# PiZeroHifi.net
KiCad netlist of a schematic drawn in EAGLE
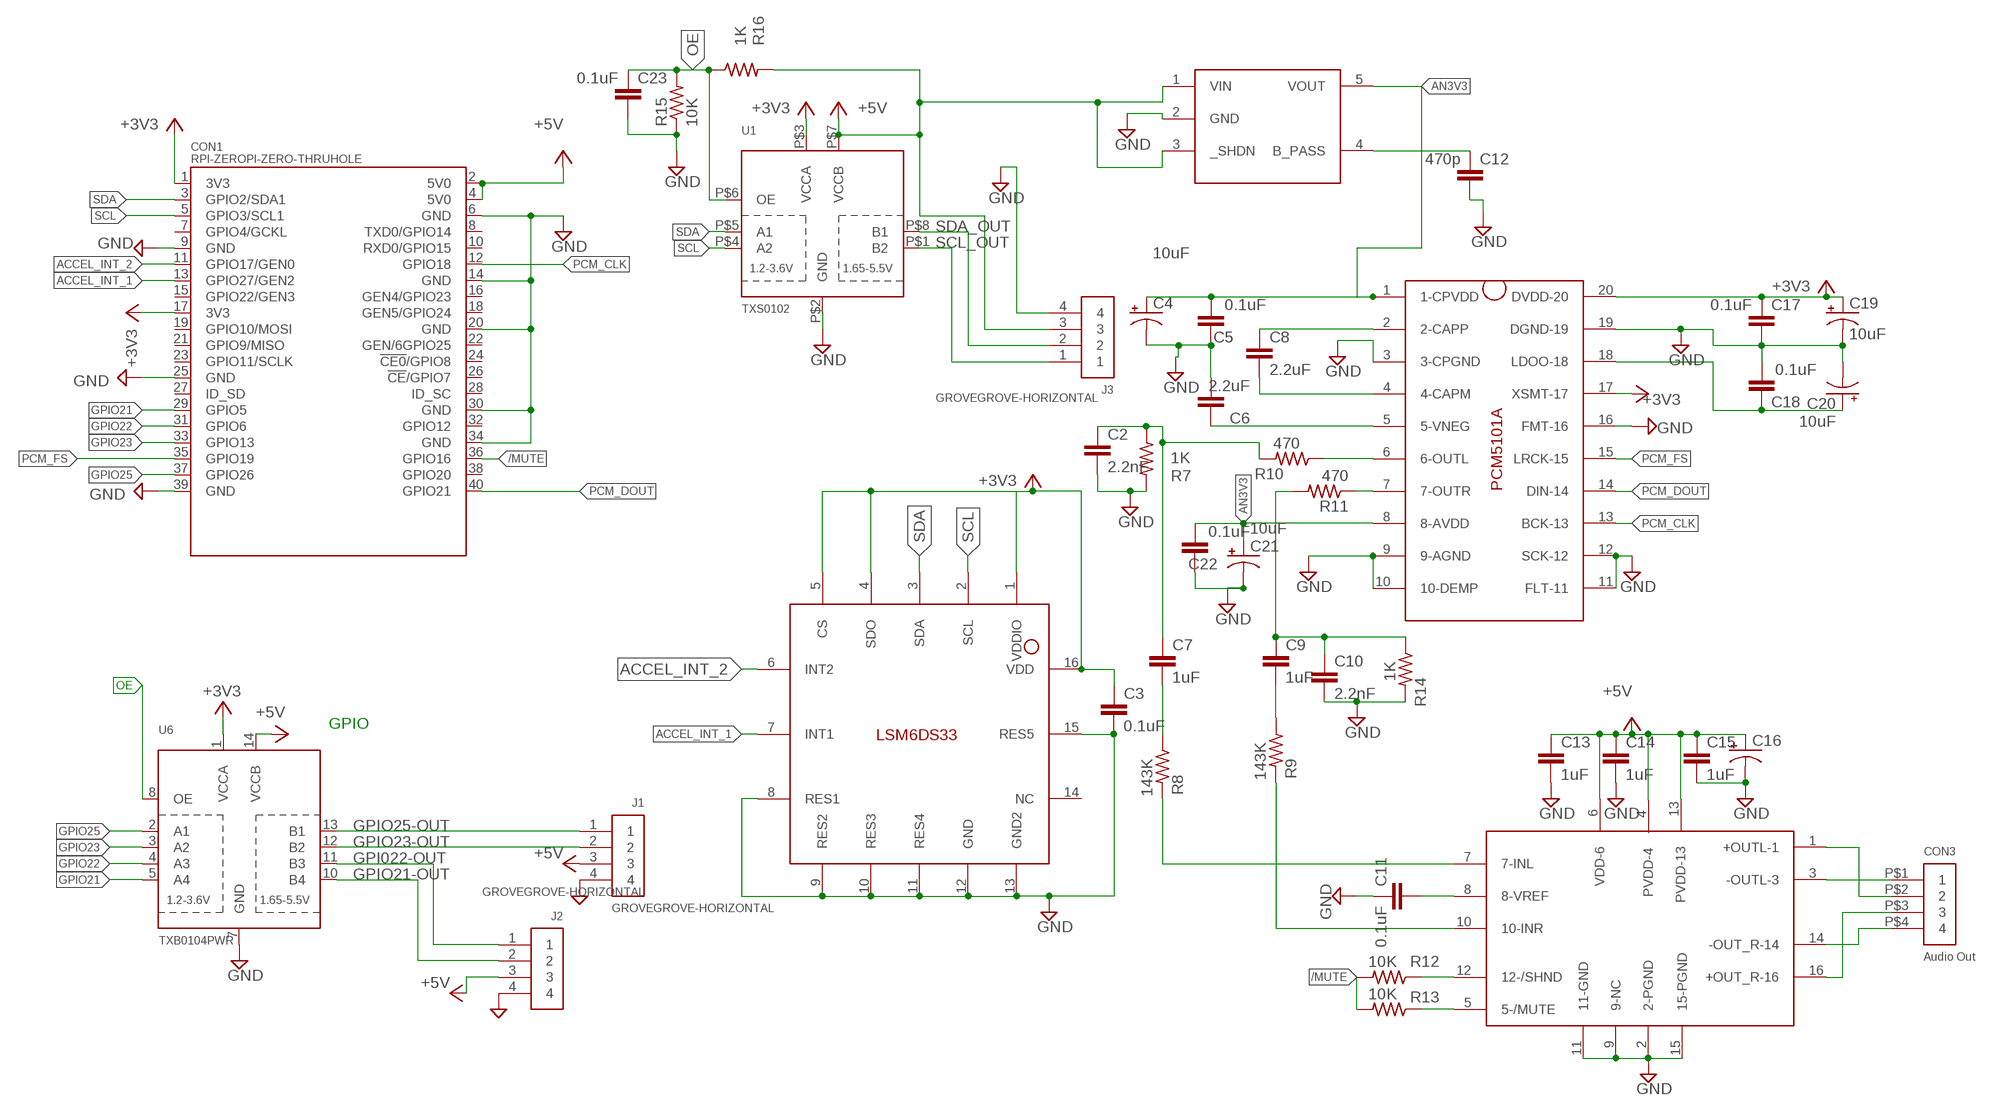
[diagram p0: schematic, sheet 1]

(export (version "E")
  (design (tool "Eeschema 10.0.6"))
  (components
    (comp (ref "C2")
      (value "2.2nF")
      (footprint "eagle-import:C0603")
      (fields (field (name "MF") "YAGEO") (field (name "MPN") "CC0603KRX7R9BB222"))
      (libsource (lib "eagle-import") (part "C-EUC0603"))
    )
    (comp (ref "C3")
      (value "0.1uF")
      (footprint "eagle-import:C0603")
      (fields (field (name "MF") "YAGEO") (field (name "MPN") "CC0603KRX7R7BB104"))
      (libsource (lib "eagle-import") (part "C-EUC0603"))
    )
    (comp (ref "C4")
      (value "10uF")
      (footprint "eagle-import:EIA3216")
      (fields (field (name "MF") "AVX") (field (name "MPN") "08053D106KAT2A"))
      (libsource (lib "eagle-import") (part "CAP-POLARISED1206-POLAR"))
    )
    (comp (ref "C5")
      (value "0.1uF")
      (footprint "eagle-import:C0603")
      (fields (field (name "MF") "YAGEO") (field (name "MPN") "CC0603KRX7R7BB104"))
      (libsource (lib "eagle-import") (part "C-EUC0603"))
    )
    (comp (ref "C6")
      (value "2.2uF")
      (footprint "eagle-import:C0603")
      (libsource (lib "eagle-import") (part "C-EUC0603"))
    )
    (comp (ref "C7")
      (value "1uF")
      (footprint "eagle-import:C0603")
      (fields (field (name "MF") "AVX") (field (name "MPN") "06033C104JAT2A"))
      (libsource (lib "eagle-import") (part "C-EUC0603"))
    )
    (comp (ref "C8")
      (value "2.2uF")
      (footprint "eagle-import:C0603")
      (libsource (lib "eagle-import") (part "C-EUC0603"))
    )
    (comp (ref "C9")
      (value "1uF")
      (footprint "eagle-import:C0603")
      (fields (field (name "MF") "AVX") (field (name "MPN") "06033C104JAT2A"))
      (libsource (lib "eagle-import") (part "C-EUC0603"))
    )
    (comp (ref "C10")
      (value "2.2nF")
      (footprint "eagle-import:C0603")
      (fields (field (name "MF") "YAGEO") (field (name "MPN") "CC0603KRX7R9BB222"))
      (libsource (lib "eagle-import") (part "C-EUC0603"))
    )
    (comp (ref "C11")
      (value "0.1uF")
      (footprint "eagle-import:C0603")
      (fields (field (name "MF") "YAGEO") (field (name "MPN") "CC0603KRX7R7BB104"))
      (libsource (lib "eagle-import") (part "C-EUC0603"))
    )
    (comp (ref "C12")
      (value "470p")
      (footprint "eagle-import:C0603")
      (fields (field (name "MF") "AVX") (field (name "MPN") "06035C471KAT2A"))
      (libsource (lib "eagle-import") (part "C-EUC0603"))
    )
    (comp (ref "C13")
      (value "1uF")
      (footprint "eagle-import:C0603")
      (fields (field (name "MF") "AVX") (field (name "MPN") "06033C104JAT2A"))
      (libsource (lib "eagle-import") (part "C-EUC0603"))
    )
    (comp (ref "C14")
      (value "1uF")
      (footprint "eagle-import:C0603")
      (fields (field (name "MF") "AVX") (field (name "MPN") "06033C104JAT2A"))
      (libsource (lib "eagle-import") (part "C-EUC0603"))
    )
    (comp (ref "C15")
      (value "1uF")
      (footprint "eagle-import:C0603")
      (fields (field (name "MF") "AVX") (field (name "MPN") "06033C104JAT2A"))
      (libsource (lib "eagle-import") (part "C-EUC0603"))
    )
    (comp (ref "C16")
      (value "1500uF")
      (footprint "eagle-import:CAP8MMX3.5MMX20MM")
      (libsource (lib "eagle-import") (part "WURTH-CAP"))
    )
    (comp (ref "C17")
      (value "0.1uF")
      (footprint "eagle-import:C0603")
      (fields (field (name "MF") "YAGEO") (field (name "MPN") "CC0603KRX7R7BB104"))
      (libsource (lib "eagle-import") (part "C-EUC0603"))
    )
    (comp (ref "C18")
      (value "0.1uF")
      (footprint "eagle-import:C0603")
      (fields (field (name "MF") "YAGEO") (field (name "MPN") "CC0603KRX7R7BB104"))
      (libsource (lib "eagle-import") (part "C-EUC0603"))
    )
    (comp (ref "C19")
      (value "10uF")
      (footprint "eagle-import:EIA3216")
      (fields (field (name "MF") "AVX") (field (name "MPN") "08053D106KAT2A"))
      (libsource (lib "eagle-import") (part "CAP-POLARISED1206-POLAR"))
    )
    (comp (ref "C20")
      (value "10uF")
      (footprint "eagle-import:EIA3216")
      (fields (field (name "MF") "AVX") (field (name "MPN") "08053D106KAT2A"))
      (libsource (lib "eagle-import") (part "CAP-POLARISED1206-POLAR"))
    )
    (comp (ref "C21")
      (value "10uF")
      (footprint "eagle-import:EIA3216")
      (fields (field (name "MF") "AVX") (field (name "MPN") "08053D106KAT2A"))
      (libsource (lib "eagle-import") (part "CAP-POLARISED1206-POLAR"))
    )
    (comp (ref "C22")
      (value "0.1uF")
      (footprint "eagle-import:C0603")
      (fields (field (name "MF") "YAGEO") (field (name "MPN") "CC0603KRX7R7BB104"))
      (libsource (lib "eagle-import") (part "C-EUC0603"))
    )
    (comp (ref "C23")
      (value "0.1uF")
      (footprint "eagle-import:C0603")
      (fields (field (name "MF") "YAGEO") (field (name "MPN") "CC0603KRX7R7BB104"))
      (libsource (lib "eagle-import") (part "C-EUC0603"))
    )
    (comp (ref "CON1")
      (value "RPI-ZEROPI-ZERO-THRUHOLE")
      (footprint "eagle-import:RASPBERRYPI_ZERO_THRUHOLE")
      (fields (field (name "MPN") "ADA2243"))
      (libsource (lib "eagle-import") (part "RPI-ZEROPI-ZERO-THRUHOLE"))
    )
    (comp (ref "CON3")
      (value "Audio Out")
      (footprint "eagle-import:TERM-4P-SIDE-5.08MM")
      (libsource (lib "eagle-import") (part "SCREW-TERM-4X5.08MM"))
    )
    (comp (ref "J1")
      (value "GROVEGROVE-HORIZONTAL")
      (footprint "eagle-import:JST-4-PTH")
      (libsource (lib "eagle-import") (part "GROVEGROVE-HORIZONTAL"))
    )
    (comp (ref "J2")
      (value "GROVEGROVE-HORIZONTAL")
      (footprint "eagle-import:JST-4-PTH")
      (libsource (lib "eagle-import") (part "GROVEGROVE-HORIZONTAL"))
    )
    (comp (ref "J3")
      (value "GROVEGROVE-HORIZONTAL")
      (footprint "eagle-import:JST-4-PTH")
      (libsource (lib "eagle-import") (part "GROVEGROVE-HORIZONTAL"))
    )
    (comp (ref "R7")
      (value "1K")
      (footprint "eagle-import:R0603")
      (fields (field (name "MF") "MULTICOMP PRO") (field (name "MPN") "MCWR06X1001FTL"))
      (libsource (lib "eagle-import") (part "R-US_R0603"))
    )
    (comp (ref "R8")
      (value "143K")
      (footprint "eagle-import:R0603")
      (fields (field (name "MF") "PANASONIC") (field (name "MPN") "ERJ3EKF1433V"))
      (libsource (lib "eagle-import") (part "R-US_R0603"))
    )
    (comp (ref "R9")
      (value "143K")
      (footprint "eagle-import:R0603")
      (fields (field (name "MF") "PANASONIC") (field (name "MPN") "ERJ3EKF1433V"))
      (libsource (lib "eagle-import") (part "R-US_R0603"))
    )
    (comp (ref "R10")
      (value "470")
      (footprint "eagle-import:R0603")
      (fields (field (name "MF") "VISHAY") (field (name "MPN") "CRCW0603470RFKEA"))
      (libsource (lib "eagle-import") (part "R-US_R0603"))
    )
    (comp (ref "R11")
      (value "470")
      (footprint "eagle-import:R0603")
      (fields (field (name "MF") "VISHAY") (field (name "MPN") "CRCW0603470RFKEA"))
      (libsource (lib "eagle-import") (part "R-US_R0603"))
    )
    (comp (ref "R12")
      (value "10K")
      (footprint "eagle-import:R0603")
      (fields (field (name "MF") "YAGEO") (field (name "MPN") "RC0603FR-0710KL"))
      (libsource (lib "eagle-import") (part "R-US_R0603"))
    )
    (comp (ref "R13")
      (value "10K")
      (footprint "eagle-import:R0603")
      (fields (field (name "MF") "YAGEO") (field (name "MPN") "RC0603FR-0710KL"))
      (libsource (lib "eagle-import") (part "R-US_R0603"))
    )
    (comp (ref "R14")
      (value "1K")
      (footprint "eagle-import:R0603")
      (fields (field (name "MF") "MULTICOMP PRO") (field (name "MPN") "MCWR06X1001FTL"))
      (libsource (lib "eagle-import") (part "R-US_R0603"))
    )
    (comp (ref "R15")
      (value "10K")
      (footprint "eagle-import:R0603")
      (fields (field (name "MF") "YAGEO") (field (name "MPN") "RC0603FR-0710KL"))
      (libsource (lib "eagle-import") (part "R-US_R0603"))
    )
    (comp (ref "R16")
      (value "1K")
      (footprint "eagle-import:R0603")
      (fields (field (name "MF") "MULTICOMP PRO") (field (name "MPN") "MCWR06X1001FTL"))
      (libsource (lib "eagle-import") (part "R-US_R0603"))
    )
    (comp (ref "U1")
      (value "TXS0102")
      (footprint "eagle-import:VFSOP-8")
      (libsource (lib "eagle-import") (part "TXS0102"))
    )
    (comp (ref "U2")
      (value "LSM6DS33")
      (footprint "eagle-import:LGA-16-3X3")
      (fields (field (name "MPN") "LSM6DS33TR"))
      (libsource (lib "eagle-import") (part "LSM6DS33LGA-16-3X3"))
    )
    (comp (ref "U3")
      (value "TC1014-3.3V")
      (footprint "eagle-import:GHI-IC_SOT23-5(MICROCHIP)")
      (fields (field (name "MF") "MICROCHIP") (field (name "MPN") "TC1014-3.3VCT713"))
      (libsource (lib "eagle-import") (part "TC1014-3.3V"))
    )
    (comp (ref "U4")
      (value "PCM5101A")
      (footprint "eagle-import:TSSOP20-0.65-6.5X4.4MM")
      (fields (field (name "MPN") "PCM5101APWR"))
      (libsource (lib "eagle-import") (part "PCM5101A"))
    )
    (comp (ref "U5")
      (value "PAM8403")
      (footprint "eagle-import:SOP-16")
      (fields (field (name "MPN") "PAM8403DR") (field (name "MF") "DIODES INC."))
      (libsource (lib "eagle-import") (part "PAM8403"))
    )
    (comp (ref "U6")
      (value "TXB0104PWR")
      (footprint "eagle-import:TSSOP14")
      (fields (field (name "MF") "TEXAS INSTRUMENTS") (field (name "MPN") "TXB0104PWR ."))
      (libsource (lib "eagle-import") (part "TXB0104PWR"))
    )
  )
  (nets
    (net (code "1") (name "+3V3") (class "Default")
      (node (ref "C17") (pin "2") (pinfunction "2_2") (pintype "passive"))
      (node (ref "C19") (pin "+") (pinfunction "+_+") (pintype "passive"))
      (node (ref "C3") (pin "1") (pinfunction "1_1") (pintype "passive"))
      (node (ref "CON1") (pin "1") (pinfunction "3V3_1") (pintype "power_in"))
      (node (ref "CON1") (pin "17") (pinfunction "3V3_17") (pintype "power_in"))
      (node (ref "U1") (pin "P$3") (pinfunction "VCCA_P$3") (pintype "bidirectional"))
      (node (ref "U2") (pin "1") (pinfunction "VDDIO_1") (pintype "bidirectional"))
      (node (ref "U2") (pin "16") (pinfunction "VDD_16") (pintype "bidirectional"))
      (node (ref "U2") (pin "4") (pinfunction "SDO_4") (pintype "bidirectional"))
      (node (ref "U2") (pin "5") (pinfunction "CS_5") (pintype "bidirectional"))
      (node (ref "U4") (pin "17") (pinfunction "XSMT-17_17") (pintype "bidirectional"))
      (node (ref "U4") (pin "20") (pinfunction "DVDD-20_20") (pintype "bidirectional"))
      (node (ref "U6") (pin "1") (pinfunction "VCCA_1") (pintype "bidirectional"))
    )
    (net (code "2") (name "+5V") (class "Default")
      (node (ref "C13") (pin "1") (pinfunction "1_1") (pintype "passive"))
      (node (ref "C14") (pin "1") (pinfunction "1_1") (pintype "passive"))
      (node (ref "C15") (pin "1") (pinfunction "1_1") (pintype "passive"))
      (node (ref "C16") (pin "P$1") (pinfunction "+_P$1") (pintype "passive"))
      (node (ref "CON1") (pin "2") (pinfunction "5V0_2") (pintype "power_in"))
      (node (ref "CON1") (pin "4") (pinfunction "5V0_4") (pintype "power_in"))
      (node (ref "J1") (pin "3") (pinfunction "3_3") (pintype "bidirectional"))
      (node (ref "J2") (pin "3") (pinfunction "3_3") (pintype "bidirectional"))
      (node (ref "J3") (pin "3") (pinfunction "3_3") (pintype "bidirectional"))
      (node (ref "R16") (pin "2") (pinfunction "2_2") (pintype "passive"))
      (node (ref "U1") (pin "P$7") (pinfunction "VCCB_P$7") (pintype "bidirectional"))
      (node (ref "U3") (pin "1") (pinfunction "VIN_1") (pintype "bidirectional"))
      (node (ref "U3") (pin "3") (pinfunction "_SHDN_3") (pintype "bidirectional"))
      (node (ref "U5") (pin "13") (pinfunction "PVDD-13_13") (pintype "bidirectional"))
      (node (ref "U5") (pin "4") (pinfunction "PVDD-4_4") (pintype "bidirectional"))
      (node (ref "U5") (pin "6") (pinfunction "VDD-6_6") (pintype "bidirectional"))
      (node (ref "U6") (pin "14") (pinfunction "VCCB_14") (pintype "bidirectional"))
    )
    (net (code "3") (name "/GPI022-OUT") (class "Default")
      (node (ref "J2") (pin "1") (pinfunction "1_1") (pintype "bidirectional"))
      (node (ref "U6") (pin "11") (pinfunction "B3_11") (pintype "bidirectional"))
    )
    (net (code "4") (name "/GPIO21-OUT") (class "Default")
      (node (ref "J2") (pin "2") (pinfunction "2_2") (pintype "bidirectional"))
      (node (ref "U6") (pin "10") (pinfunction "B4_10") (pintype "bidirectional"))
    )
    (net (code "5") (name "/GPIO23-OUT") (class "Default")
      (node (ref "J1") (pin "2") (pinfunction "2_2") (pintype "bidirectional"))
      (node (ref "U6") (pin "12") (pinfunction "B2_12") (pintype "bidirectional"))
    )
    (net (code "6") (name "/GPIO25-OUT") (class "Default")
      (node (ref "J1") (pin "1") (pinfunction "1_1") (pintype "bidirectional"))
      (node (ref "U6") (pin "13") (pinfunction "B1_13") (pintype "bidirectional"))
    )
    (net (code "7") (name "/SCL_OUT") (class "Default")
      (node (ref "J3") (pin "1") (pinfunction "1_1") (pintype "bidirectional"))
      (node (ref "U1") (pin "P$1") (pinfunction "B2_P$1") (pintype "bidirectional"))
    )
    (net (code "8") (name "/SDA_OUT") (class "Default")
      (node (ref "J3") (pin "2") (pinfunction "2_2") (pintype "bidirectional"))
      (node (ref "U1") (pin "P$8") (pinfunction "B1_P$8") (pintype "bidirectional"))
    )
    (net (code "9") (name "ACCEL_INT_1") (class "Default")
      (node (ref "CON1") (pin "13") (pinfunction "GPIO27/GEN2_13") (pintype "bidirectional"))
      (node (ref "U2") (pin "7") (pinfunction "INT1_7") (pintype "bidirectional"))
    )
    (net (code "10") (name "ACCEL_INT_2") (class "Default")
      (node (ref "CON1") (pin "11") (pinfunction "GPIO17/GEN0_11") (pintype "bidirectional"))
      (node (ref "U2") (pin "6") (pinfunction "INT2_6") (pintype "bidirectional"))
    )
    (net (code "11") (name "AN3V3") (class "Default")
      (node (ref "C21") (pin "+") (pinfunction "+_+") (pintype "passive"))
      (node (ref "C22") (pin "2") (pinfunction "2_2") (pintype "passive"))
      (node (ref "C4") (pin "+") (pinfunction "+_+") (pintype "passive"))
      (node (ref "C5") (pin "2") (pinfunction "2_2") (pintype "passive"))
      (node (ref "U3") (pin "5") (pinfunction "VOUT_5") (pintype "bidirectional"))
      (node (ref "U4") (pin "1") (pinfunction "1-CPVDD_1") (pintype "bidirectional"))
      (node (ref "U4") (pin "8") (pinfunction "8-AVDD_8") (pintype "bidirectional"))
    )
    (net (code "12") (name "GND") (class "Default")
      (node (ref "C10") (pin "2") (pinfunction "2_2") (pintype "passive"))
      (node (ref "C11") (pin "2") (pinfunction "2_2") (pintype "passive"))
      (node (ref "C12") (pin "1") (pinfunction "1_1") (pintype "passive"))
      (node (ref "C13") (pin "2") (pinfunction "2_2") (pintype "passive"))
      (node (ref "C14") (pin "2") (pinfunction "2_2") (pintype "passive"))
      (node (ref "C15") (pin "2") (pinfunction "2_2") (pintype "passive"))
      (node (ref "C16") (pin "P$2") (pinfunction "-_P$2") (pintype "passive"))
      (node (ref "C17") (pin "1") (pinfunction "1_1") (pintype "passive"))
      (node (ref "C18") (pin "2") (pinfunction "2_2") (pintype "passive"))
      (node (ref "C19") (pin "-") (pinfunction "-_-") (pintype "passive"))
      (node (ref "C2") (pin "2") (pinfunction "2_2") (pintype "passive"))
      (node (ref "C20") (pin "-") (pinfunction "-_-") (pintype "passive"))
      (node (ref "C21") (pin "-") (pinfunction "-_-") (pintype "passive"))
      (node (ref "C22") (pin "1") (pinfunction "1_1") (pintype "passive"))
      (node (ref "C23") (pin "1") (pinfunction "1_1") (pintype "passive"))
      (node (ref "C3") (pin "2") (pinfunction "2_2") (pintype "passive"))
      (node (ref "C4") (pin "-") (pinfunction "-_-") (pintype "passive"))
      (node (ref "C5") (pin "1") (pinfunction "1_1") (pintype "passive"))
      (node (ref "C6") (pin "2") (pinfunction "2_2") (pintype "passive"))
      (node (ref "CON1") (pin "14") (pinfunction "GND_14") (pintype "power_in"))
      (node (ref "CON1") (pin "20") (pinfunction "GND_20") (pintype "power_in"))
      (node (ref "CON1") (pin "25") (pinfunction "GND_25") (pintype "power_in"))
      (node (ref "CON1") (pin "30") (pinfunction "GND_30") (pintype "power_in"))
      (node (ref "CON1") (pin "34") (pinfunction "GND_34") (pintype "power_in"))
      (node (ref "CON1") (pin "39") (pinfunction "GND_39") (pintype "power_in"))
      (node (ref "CON1") (pin "6") (pinfunction "GND_6") (pintype "power_in"))
      (node (ref "CON1") (pin "9") (pinfunction "GND_9") (pintype "power_in"))
      (node (ref "J1") (pin "4") (pinfunction "4_4") (pintype "bidirectional"))
      (node (ref "J2") (pin "4") (pinfunction "4_4") (pintype "bidirectional"))
      (node (ref "J3") (pin "4") (pinfunction "4_4") (pintype "bidirectional"))
      (node (ref "R14") (pin "2") (pinfunction "2_2") (pintype "passive"))
      (node (ref "R15") (pin "1") (pinfunction "1_1") (pintype "passive"))
      (node (ref "R7") (pin "2") (pinfunction "2_2") (pintype "passive"))
      (node (ref "U1") (pin "P$2") (pinfunction "GND_P$2") (pintype "bidirectional"))
      (node (ref "U2") (pin "10") (pinfunction "RES3_10") (pintype "bidirectional"))
      (node (ref "U2") (pin "11") (pinfunction "RES4_11") (pintype "bidirectional"))
      (node (ref "U2") (pin "12") (pinfunction "GND_12") (pintype "bidirectional"))
      (node (ref "U2") (pin "13") (pinfunction "GND2_13") (pintype "bidirectional"))
      (node (ref "U2") (pin "15") (pinfunction "RES5_15") (pintype "bidirectional"))
      (node (ref "U2") (pin "8") (pinfunction "RES1_8") (pintype "bidirectional"))
      (node (ref "U2") (pin "9") (pinfunction "RES2_9") (pintype "bidirectional"))
      (node (ref "U3") (pin "2") (pinfunction "GND_2") (pintype "bidirectional"))
      (node (ref "U4") (pin "10") (pinfunction "10-DEMP_10") (pintype "bidirectional"))
      (node (ref "U4") (pin "11") (pinfunction "FLT-11_11") (pintype "bidirectional"))
      (node (ref "U4") (pin "12") (pinfunction "SCK-12_12") (pintype "bidirectional"))
      (node (ref "U4") (pin "16") (pinfunction "FMT-16_16") (pintype "bidirectional"))
      (node (ref "U4") (pin "19") (pinfunction "DGND-19_19") (pintype "bidirectional"))
      (node (ref "U4") (pin "3") (pinfunction "3-CPGND_3") (pintype "bidirectional"))
      (node (ref "U4") (pin "9") (pinfunction "9-AGND_9") (pintype "bidirectional"))
      (node (ref "U5") (pin "11") (pinfunction "11-GND_11") (pintype "bidirectional"))
      (node (ref "U5") (pin "15") (pinfunction "15-PGND_15") (pintype "bidirectional"))
      (node (ref "U5") (pin "2") (pinfunction "2-PGND_2") (pintype "bidirectional"))
      (node (ref "U5") (pin "9") (pinfunction "9-NC_9") (pintype "bidirectional"))
      (node (ref "U6") (pin "7") (pinfunction "GND_7") (pintype "bidirectional"))
    )
    (net (code "13") (name "GPIO21") (class "Default")
      (node (ref "CON1") (pin "29") (pinfunction "GPIO5_29") (pintype "bidirectional"))
      (node (ref "U6") (pin "5") (pinfunction "A4_5") (pintype "bidirectional"))
    )
    (net (code "14") (name "GPIO22") (class "Default")
      (node (ref "CON1") (pin "31") (pinfunction "GPIO6_31") (pintype "bidirectional"))
      (node (ref "U6") (pin "4") (pinfunction "A3_4") (pintype "bidirectional"))
    )
    (net (code "15") (name "GPIO23") (class "Default")
      (node (ref "CON1") (pin "33") (pinfunction "GPIO13_33") (pintype "bidirectional"))
      (node (ref "U6") (pin "3") (pinfunction "A2_3") (pintype "bidirectional"))
    )
    (net (code "16") (name "GPIO25") (class "Default")
      (node (ref "CON1") (pin "37") (pinfunction "GPIO26_37") (pintype "bidirectional"))
      (node (ref "U6") (pin "2") (pinfunction "A1_2") (pintype "bidirectional"))
    )
    (net (code "17") (name "Net-(C2-Pad1)") (class "Default")
      (node (ref "C2") (pin "1") (pinfunction "1_1") (pintype "passive"))
      (node (ref "C7") (pin "1") (pinfunction "1_1") (pintype "passive"))
      (node (ref "R10") (pin "2") (pinfunction "2_2") (pintype "passive"))
      (node (ref "R7") (pin "1") (pinfunction "1_1") (pintype "passive"))
    )
    (net (code "18") (name "Net-(C7-Pad2)") (class "Default")
      (node (ref "C7") (pin "2") (pinfunction "2_2") (pintype "passive"))
      (node (ref "R8") (pin "1") (pinfunction "1_1") (pintype "passive"))
    )
    (net (code "19") (name "Net-(C9-Pad2)") (class "Default")
      (node (ref "C9") (pin "2") (pinfunction "2_2") (pintype "passive"))
      (node (ref "R9") (pin "1") (pinfunction "1_1") (pintype "passive"))
    )
    (net (code "20") (name "Net-(C10-Pad1)") (class "Default")
      (node (ref "C10") (pin "1") (pinfunction "1_1") (pintype "passive"))
      (node (ref "C9") (pin "1") (pinfunction "1_1") (pintype "passive"))
      (node (ref "R11") (pin "2") (pinfunction "2_2") (pintype "passive"))
      (node (ref "R14") (pin "1") (pinfunction "1_1") (pintype "passive"))
    )
    (net (code "21") (name "Net-(CON3-1)") (class "Default")
      (node (ref "CON3") (pin "P$1") (pinfunction "1_P$1") (pintype "bidirectional"))
      (node (ref "U5") (pin "3") (pinfunction "-OUTL-3_3") (pintype "bidirectional"))
    )
    (net (code "22") (name "Net-(CON3-2)") (class "Default")
      (node (ref "CON3") (pin "P$2") (pinfunction "2_P$2") (pintype "bidirectional"))
      (node (ref "U5") (pin "1") (pinfunction "+OUTL-1_1") (pintype "bidirectional"))
    )
    (net (code "23") (name "Net-(CON3-3)") (class "Default")
      (node (ref "CON3") (pin "P$3") (pinfunction "3_P$3") (pintype "bidirectional"))
      (node (ref "U5") (pin "16") (pinfunction "+OUT_R-16_16") (pintype "bidirectional"))
    )
    (net (code "24") (name "Net-(CON3-4)") (class "Default")
      (node (ref "CON3") (pin "P$4") (pinfunction "4_P$4") (pintype "bidirectional"))
      (node (ref "U5") (pin "14") (pinfunction "-OUT_R-14_14") (pintype "bidirectional"))
    )
    (net (code "25") (name "Net-(U3-B_PASS)") (class "Default")
      (node (ref "C12") (pin "2") (pinfunction "2_2") (pintype "passive"))
      (node (ref "U3") (pin "4") (pinfunction "B_PASS_4") (pintype "bidirectional"))
    )
    (net (code "26") (name "Net-(U4-2-CAPP)") (class "Default")
      (node (ref "C8") (pin "1") (pinfunction "1_1") (pintype "passive"))
      (node (ref "U4") (pin "2") (pinfunction "2-CAPP_2") (pintype "bidirectional"))
    )
    (net (code "27") (name "Net-(U4-4-CAPM)") (class "Default")
      (node (ref "C8") (pin "2") (pinfunction "2_2") (pintype "passive"))
      (node (ref "U4") (pin "4") (pinfunction "4-CAPM_4") (pintype "bidirectional"))
    )
    (net (code "28") (name "Net-(U4-5-VNEG)") (class "Default")
      (node (ref "C6") (pin "1") (pinfunction "1_1") (pintype "passive"))
      (node (ref "U4") (pin "5") (pinfunction "5-VNEG_5") (pintype "bidirectional"))
    )
    (net (code "29") (name "Net-(U4-6-OUTL)") (class "Default")
      (node (ref "R10") (pin "1") (pinfunction "1_1") (pintype "passive"))
      (node (ref "U4") (pin "6") (pinfunction "6-OUTL_6") (pintype "bidirectional"))
    )
    (net (code "30") (name "Net-(U4-7-OUTR)") (class "Default")
      (node (ref "R11") (pin "1") (pinfunction "1_1") (pintype "passive"))
      (node (ref "U4") (pin "7") (pinfunction "7-OUTR_7") (pintype "bidirectional"))
    )
    (net (code "31") (name "Net-(U4-LDOO-18)") (class "Default")
      (node (ref "C18") (pin "1") (pinfunction "1_1") (pintype "passive"))
      (node (ref "C20") (pin "+") (pinfunction "+_+") (pintype "passive"))
      (node (ref "U4") (pin "18") (pinfunction "LDOO-18_18") (pintype "bidirectional"))
    )
    (net (code "32") (name "Net-(U5-5-{slash}MUTE)") (class "Default")
      (node (ref "R13") (pin "1") (pinfunction "1_1") (pintype "passive"))
      (node (ref "U5") (pin "5") (pinfunction "5-/MUTE_5") (pintype "bidirectional"))
    )
    (net (code "33") (name "Net-(U5-7-INL)") (class "Default")
      (node (ref "R8") (pin "2") (pinfunction "2_2") (pintype "passive"))
      (node (ref "U5") (pin "7") (pinfunction "7-INL_7") (pintype "bidirectional"))
    )
    (net (code "34") (name "Net-(U5-8-VREF)") (class "Default")
      (node (ref "C11") (pin "1") (pinfunction "1_1") (pintype "passive"))
      (node (ref "U5") (pin "8") (pinfunction "8-VREF_8") (pintype "bidirectional"))
    )
    (net (code "35") (name "Net-(U5-10-INR)") (class "Default")
      (node (ref "R9") (pin "2") (pinfunction "2_2") (pintype "passive"))
      (node (ref "U5") (pin "10") (pinfunction "10-INR_10") (pintype "bidirectional"))
    )
    (net (code "36") (name "Net-(U5-12-{slash}SHND)") (class "Default")
      (node (ref "R12") (pin "1") (pinfunction "1_1") (pintype "passive"))
      (node (ref "U5") (pin "12") (pinfunction "12-/SHND_12") (pintype "bidirectional"))
    )
    (net (code "37") (name "OE") (class "Default")
      (node (ref "C23") (pin "2") (pinfunction "2_2") (pintype "passive"))
      (node (ref "R15") (pin "2") (pinfunction "2_2") (pintype "passive"))
      (node (ref "R16") (pin "1") (pinfunction "1_1") (pintype "passive"))
      (node (ref "U1") (pin "P$6") (pinfunction "OE_P$6") (pintype "bidirectional"))
      (node (ref "U6") (pin "8") (pinfunction "OE_8") (pintype "bidirectional"))
    )
    (net (code "38") (name "PCM_CLK") (class "Default")
      (node (ref "CON1") (pin "12") (pinfunction "GPIO18_12") (pintype "bidirectional"))
      (node (ref "U4") (pin "13") (pinfunction "BCK-13_13") (pintype "bidirectional"))
    )
    (net (code "39") (name "PCM_DOUT") (class "Default")
      (node (ref "CON1") (pin "40") (pinfunction "GPIO21_40") (pintype "bidirectional"))
      (node (ref "U4") (pin "14") (pinfunction "DIN-14_14") (pintype "bidirectional"))
    )
    (net (code "40") (name "PCM_FS") (class "Default")
      (node (ref "CON1") (pin "35") (pinfunction "GPIO19_35") (pintype "bidirectional"))
      (node (ref "U4") (pin "15") (pinfunction "LRCK-15_15") (pintype "bidirectional"))
    )
    (net (code "41") (name "SCL") (class "Default")
      (node (ref "CON1") (pin "5") (pinfunction "GPIO3/SCL1_5") (pintype "bidirectional"))
      (node (ref "U1") (pin "P$4") (pinfunction "A2_P$4") (pintype "bidirectional"))
      (node (ref "U2") (pin "2") (pinfunction "SCL_2") (pintype "bidirectional"))
    )
    (net (code "42") (name "SDA") (class "Default")
      (node (ref "CON1") (pin "3") (pinfunction "GPIO2/SDA1_3") (pintype "bidirectional"))
      (node (ref "U1") (pin "P$5") (pinfunction "A1_P$5") (pintype "bidirectional"))
      (node (ref "U2") (pin "3") (pinfunction "SDA_3") (pintype "bidirectional"))
    )
    (net (code "43") (name "unconnected-(CON1-GEN4{slash}GPIO23-Pad16)") (class "Default")
      (node (ref "CON1") (pin "16") (pinfunction "GEN4/GPIO23_16") (pintype "bidirectional"))
    )
    (net (code "44") (name "unconnected-(CON1-GEN5{slash}GPIO24-Pad18)") (class "Default")
      (node (ref "CON1") (pin "18") (pinfunction "GEN5/GPIO24_18") (pintype "bidirectional"))
    )
    (net (code "45") (name "unconnected-(CON1-GEN{slash}6GPIO25-Pad22)") (class "Default")
      (node (ref "CON1") (pin "22") (pinfunction "GEN/6GPIO25_22") (pintype "bidirectional"))
    )
    (net (code "46") (name "unconnected-(CON1-GPIO4{slash}GCKL-Pad7)") (class "Default")
      (node (ref "CON1") (pin "7") (pinfunction "GPIO4/GCKL_7") (pintype "bidirectional"))
    )
    (net (code "47") (name "unconnected-(CON1-GPIO9{slash}MISO-Pad21)") (class "Default")
      (node (ref "CON1") (pin "21") (pinfunction "GPIO9/MISO_21") (pintype "bidirectional"))
    )
    (net (code "48") (name "unconnected-(CON1-GPIO10{slash}MOSI-Pad19)") (class "Default")
      (node (ref "CON1") (pin "19") (pinfunction "GPIO10/MOSI_19") (pintype "bidirectional"))
    )
    (net (code "49") (name "unconnected-(CON1-GPIO11{slash}SCLK-Pad23)") (class "Default")
      (node (ref "CON1") (pin "23") (pinfunction "GPIO11/SCLK_23") (pintype "bidirectional"))
    )
    (net (code "50") (name "unconnected-(CON1-GPIO12-Pad32)") (class "Default")
      (node (ref "CON1") (pin "32") (pinfunction "GPIO12_32") (pintype "bidirectional"))
    )
    (net (code "51") (name "unconnected-(CON1-GPIO20-Pad38)") (class "Default")
      (node (ref "CON1") (pin "38") (pinfunction "GPIO20_38") (pintype "bidirectional"))
    )
    (net (code "52") (name "unconnected-(CON1-GPIO22{slash}GEN3-Pad15)") (class "Default")
      (node (ref "CON1") (pin "15") (pinfunction "GPIO22/GEN3_15") (pintype "bidirectional"))
    )
    (net (code "53") (name "unconnected-(CON1-ID_SC-Pad28)") (class "Default")
      (node (ref "CON1") (pin "28") (pinfunction "ID_SC_28") (pintype "bidirectional"))
    )
    (net (code "54") (name "unconnected-(CON1-ID_SD-Pad27)") (class "Default")
      (node (ref "CON1") (pin "27") (pinfunction "ID_SD_27") (pintype "bidirectional"))
    )
    (net (code "55") (name "unconnected-(CON1-RXD0{slash}GPIO15-Pad10)") (class "Default")
      (node (ref "CON1") (pin "10") (pinfunction "RXD0/GPIO15_10") (pintype "bidirectional"))
    )
    (net (code "56") (name "unconnected-(CON1-TXD0{slash}GPIO14-Pad8)") (class "Default")
      (node (ref "CON1") (pin "8") (pinfunction "TXD0/GPIO14_8") (pintype "bidirectional"))
    )
    (net (code "57") (name "unconnected-(CON1-~{CE0}{slash}GPIO8-Pad24)") (class "Default")
      (node (ref "CON1") (pin "24") (pinfunction "~{CE0}/GPIO8_24") (pintype "bidirectional"))
    )
    (net (code "58") (name "unconnected-(CON1-~{CE}{slash}GPIO7-Pad26)") (class "Default")
      (node (ref "CON1") (pin "26") (pinfunction "~{CE}/GPIO7_26") (pintype "bidirectional"))
    )
    (net (code "59") (name "unconnected-(U2-NC-Pad14)") (class "Default")
      (node (ref "U2") (pin "14") (pinfunction "NC_14") (pintype "bidirectional"))
    )
    (net (code "60") (name "{slash}MUTE") (class "Default")
      (node (ref "CON1") (pin "36") (pinfunction "GPIO16_36") (pintype "bidirectional"))
      (node (ref "R12") (pin "2") (pinfunction "2_2") (pintype "passive"))
      (node (ref "R13") (pin "2") (pinfunction "2_2") (pintype "passive"))
    )
  )
)
